# InkTime-Schematic.net
KiCad netlist of a schematic drawn in EAGLE
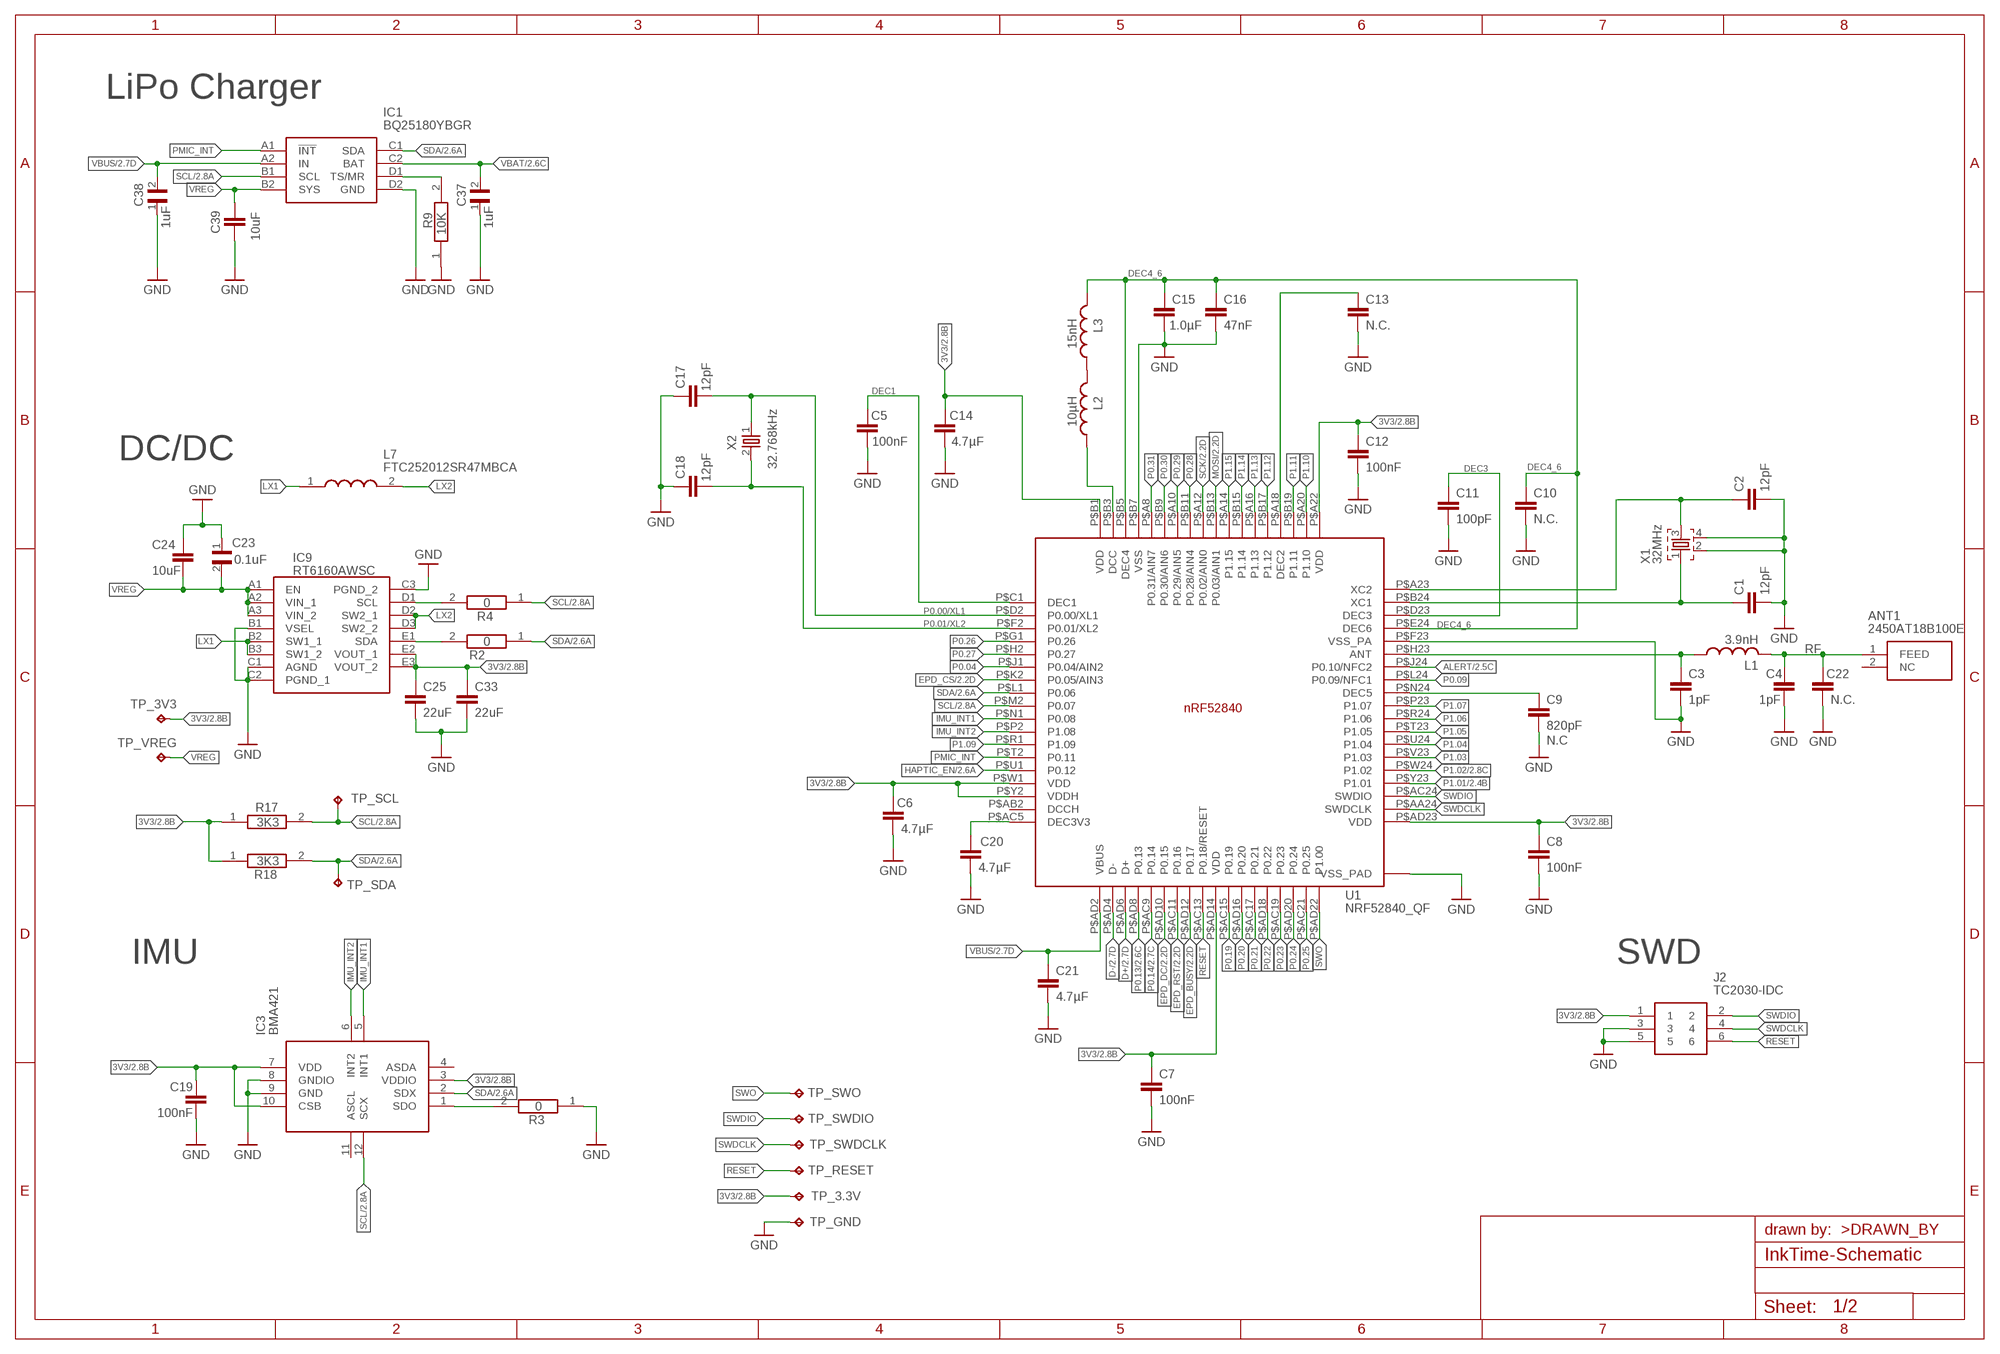
[diagram p0: schematic, sheet 1]
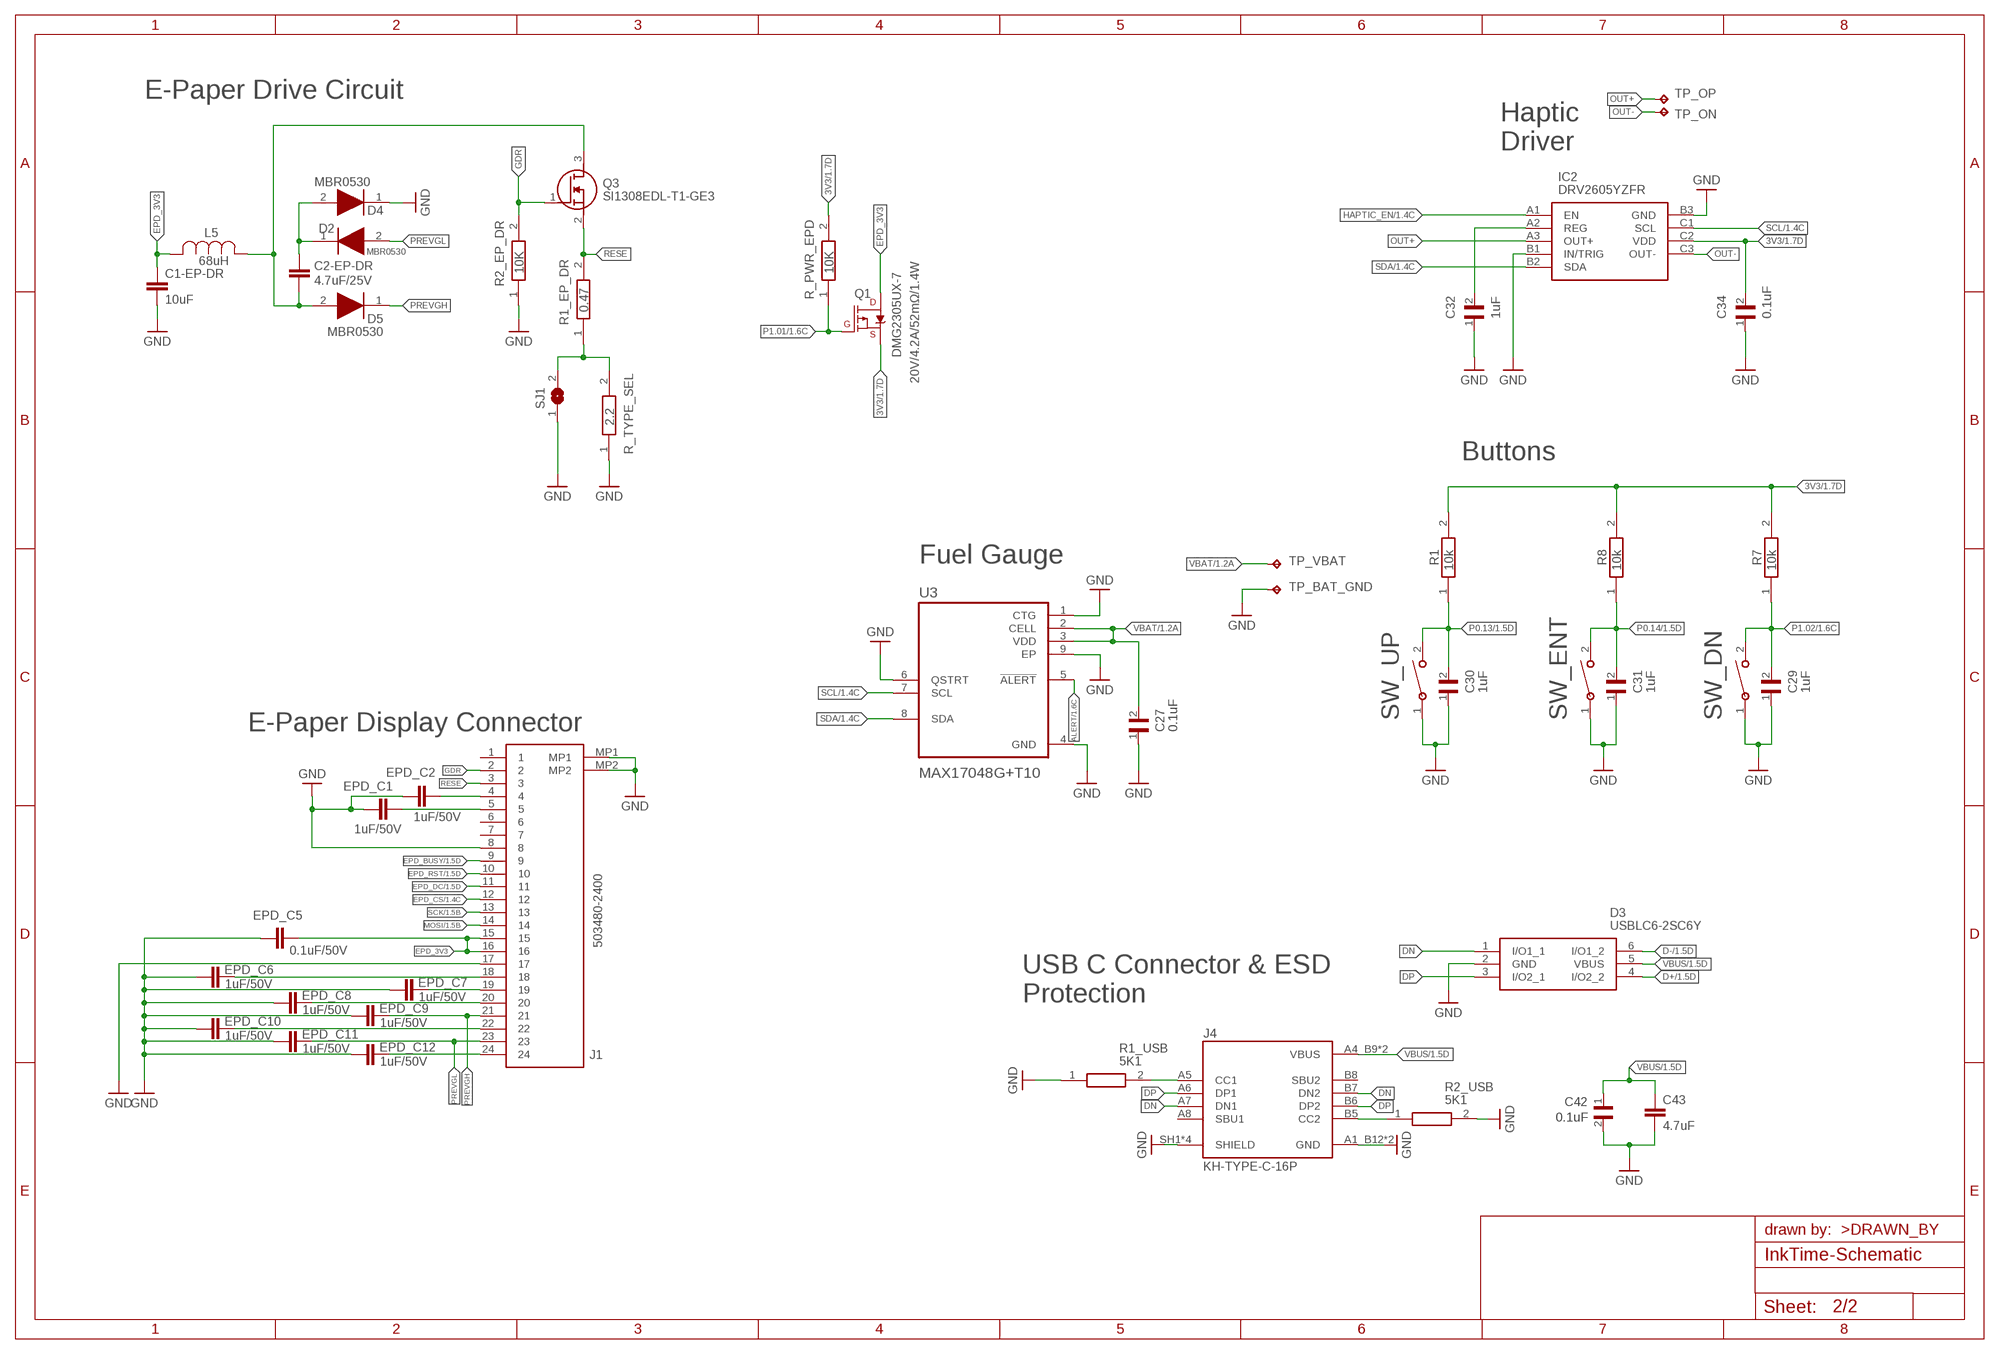
[diagram p1: schematic, sheet 2]

(export (version "E")
  (design (tool "Eeschema 10.0.6"))
  (components
    (comp (ref "ANT1")
      (value "2450AT18B100E")
      (footprint "eagle-import:2450AT18B100E_ANTC3216X140N")
      (fields (field (name "MOUSER_PART_NUMBER") "609-2450AT18B100E"))
      (libsource (lib "eagle-import") (part "2450AT18B100E_2450AT18B100E"))
    )
    (comp (ref "C1")
      (value "12pF")
      (footprint "eagle-import:NORDIC_NRF_3_RESC0201_L")
      (libsource (lib "eagle-import") (part "NORDIC_NRF_3_CAPACITOR_0201_L"))
    )
    (comp (ref "C2")
      (value "12pF")
      (footprint "eagle-import:NORDIC_NRF_3_RESC0201_L")
      (libsource (lib "eagle-import") (part "NORDIC_NRF_3_CAPACITOR_0201_L"))
    )
    (comp (ref "C3")
      (value "1pF")
      (footprint "eagle-import:NORDIC_NRF_3_RESC0201_L")
      (libsource (lib "eagle-import") (part "NORDIC_NRF_3_CAPACITOR_0201_L"))
    )
    (comp (ref "C4")
      (value "1pF")
      (footprint "eagle-import:NORDIC_NRF_3_RESC0201_L")
      (libsource (lib "eagle-import") (part "NORDIC_NRF_3_CAPACITOR_0201_L"))
    )
    (comp (ref "C5")
      (value "100nF")
      (footprint "eagle-import:NORDIC_NRF_3_RESC0201_L")
      (libsource (lib "eagle-import") (part "NORDIC_NRF_3_CAPACITOR_0201_L"))
    )
    (comp (ref "C6")
      (value "4.7µF")
      (footprint "eagle-import:NORDIC_NRF_3_RESC0402_L")
      (libsource (lib "eagle-import") (part "NORDIC_NRF_3_CAPACITOR_0402_L"))
    )
    (comp (ref "C7")
      (value "100nF")
      (footprint "eagle-import:NORDIC_NRF_3_RESC0201_L")
      (libsource (lib "eagle-import") (part "NORDIC_NRF_3_CAPACITOR_0201_L"))
    )
    (comp (ref "C8")
      (value "100nF")
      (footprint "eagle-import:NORDIC_NRF_3_RESC0201_L")
      (libsource (lib "eagle-import") (part "NORDIC_NRF_3_CAPACITOR_0201_L"))
    )
    (comp (ref "C9")
      (value "820pF")
      (footprint "eagle-import:NORDIC_NRF_3_RESC0201_L")
      (libsource (lib "eagle-import") (part "NORDIC_NRF_3_CAPACITOR_0201_L"))
    )
    (comp (ref "C10")
      (value "N.C.")
      (footprint "eagle-import:NORDIC_NRF_3_RESC0201_L")
      (libsource (lib "eagle-import") (part "NORDIC_NRF_3_CAPACITOR_0201_L"))
    )
    (comp (ref "C11")
      (value "100pF")
      (footprint "eagle-import:NORDIC_NRF_3_RESC0201_L")
      (libsource (lib "eagle-import") (part "NORDIC_NRF_3_CAPACITOR_0201_L"))
    )
    (comp (ref "C12")
      (value "100nF")
      (footprint "eagle-import:NORDIC_NRF_3_RESC0201_L")
      (libsource (lib "eagle-import") (part "NORDIC_NRF_3_CAPACITOR_0201_L"))
    )
    (comp (ref "C13")
      (value "N.C.")
      (footprint "eagle-import:NORDIC_NRF_3_RESC0201_L")
      (libsource (lib "eagle-import") (part "NORDIC_NRF_3_CAPACITOR_0201_L"))
    )
    (comp (ref "C14")
      (value "4.7µF")
      (footprint "eagle-import:NORDIC_NRF_3_RESC0402_L")
      (libsource (lib "eagle-import") (part "NORDIC_NRF_3_CAPACITOR_0402_L"))
    )
    (comp (ref "C15")
      (value "1.0µF")
      (footprint "eagle-import:NORDIC_NRF_3_RESC0402_L")
      (libsource (lib "eagle-import") (part "NORDIC_NRF_3_CAPACITOR_0402_L"))
    )
    (comp (ref "C16")
      (value "47nF")
      (footprint "eagle-import:NORDIC_NRF_3_RESC0201_L")
      (libsource (lib "eagle-import") (part "NORDIC_NRF_3_CAPACITOR_0201_L"))
    )
    (comp (ref "C17")
      (value "12pF")
      (footprint "eagle-import:NORDIC_NRF_3_RESC0201_L")
      (libsource (lib "eagle-import") (part "NORDIC_NRF_3_CAPACITOR_0201_L"))
    )
    (comp (ref "C18")
      (value "12pF")
      (footprint "eagle-import:NORDIC_NRF_3_RESC0201_L")
      (libsource (lib "eagle-import") (part "NORDIC_NRF_3_CAPACITOR_0201_L"))
    )
    (comp (ref "C19")
      (value "100nF")
      (footprint "eagle-import:NORDIC_NRF_3_RESC0201_L")
      (libsource (lib "eagle-import") (part "NORDIC_NRF_3_CAPACITOR_0201_L"))
    )
    (comp (ref "C20")
      (value "4.7µF")
      (footprint "eagle-import:NORDIC_NRF_3_RESC0402_L")
      (libsource (lib "eagle-import") (part "NORDIC_NRF_3_CAPACITOR_0402_L"))
    )
    (comp (ref "C21")
      (value "4.7µF")
      (footprint "eagle-import:NORDIC_NRF_3_RESC0402_L")
      (libsource (lib "eagle-import") (part "NORDIC_NRF_3_CAPACITOR_0402_L"))
    )
    (comp (ref "C22")
      (value "N.C.")
      (footprint "eagle-import:NORDIC_NRF_3_RESC0201_L")
      (libsource (lib "eagle-import") (part "NORDIC_NRF_3_CAPACITOR_0201_L"))
    )
    (comp (ref "C23")
      (value "0.1uF")
      (footprint "eagle-import:GRM011R60J152KE01L_1_0201")
      (libsource (lib "eagle-import") (part "GRM011R60J152KE01L_1_GRM011R60J152KE01L"))
    )
    (comp (ref "C24")
      (value "10uF")
      (footprint "eagle-import:NORDIC_NRF_3_RESC0402_L")
      (libsource (lib "eagle-import") (part "NORDIC_NRF_3_CAPACITOR_0402_L"))
    )
    (comp (ref "C25")
      (value "22uF")
      (footprint "eagle-import:NORDIC_NRF_3_RESC0402_L")
      (libsource (lib "eagle-import") (part "NORDIC_NRF_3_CAPACITOR_0402_L"))
    )
    (comp (ref "C33")
      (value "22uF")
      (footprint "eagle-import:NORDIC_NRF_3_RESC0402_L")
      (libsource (lib "eagle-import") (part "NORDIC_NRF_3_CAPACITOR_0402_L"))
    )
    (comp (ref "C37")
      (value "1uF")
      (footprint "eagle-import:GRM011R60J152KE01L_1_0201")
      (libsource (lib "eagle-import") (part "GRM011R60J152KE01L_1_GRM011R60J152KE01L"))
    )
    (comp (ref "C38")
      (value "1uF")
      (footprint "eagle-import:GRM011R60J152KE01L_1_0201")
      (libsource (lib "eagle-import") (part "GRM011R60J152KE01L_1_GRM011R60J152KE01L"))
    )
    (comp (ref "C39")
      (value "10uF")
      (footprint "eagle-import:NORDIC_NRF_3_RESC0402_L")
      (libsource (lib "eagle-import") (part "NORDIC_NRF_3_CAPACITOR_0402_L"))
    )
    (comp (ref "IC1")
      (value "BQ25180YBGR")
      (footprint "eagle-import:BQ25180YBGR_BGA8C40P2X4_100X155X50")
      (fields (field (name "MOUSER_PART_NUMBER") "595-BQ25180YBGR"))
      (libsource (lib "eagle-import") (part "BQ25180YBGR_BQ25180YBGR"))
    )
    (comp (ref "IC3")
      (value "BMA421")
      (footprint "eagle-import:BMA423_BMA423")
      (fields (field (name "ARROW_PART_NUMBER") "BMA423") (field (name "MOUSER_PART_NUMBER") "262-BMA423"))
      (libsource (lib "eagle-import") (part "BMA423_BMA423"))
    )
    (comp (ref "IC9")
      (value "RT6160AWSC")
      (footprint "eagle-import:RT6160AWSC_BGA15C40P3X5_140X230X60")
      (fields (field (name "MOUSER_PART_NUMBER") "835-RT6160AWSC"))
      (libsource (lib "eagle-import") (part "RT6160AWSC_RT6160AWSC"))
    )
    (comp (ref "J2")
      (value "TC2030-IDC")
      (footprint "eagle-import:TC2030-IDC_TC2030IDC")
      (libsource (lib "eagle-import") (part "TC2030-IDC_TC2030-IDC"))
    )
    (comp (ref "L1")
      (value "3.9nH")
      (footprint "eagle-import:NORDIC_NRF_2_RESC0402_L")
      (libsource (lib "eagle-import") (part "NORDIC_NRF_2_INDUCTOR_0402_L"))
    )
    (comp (ref "L2")
      (value "10µH")
      (footprint "eagle-import:NORDIC_NRF_2_RESC0402_L")
      (libsource (lib "eagle-import") (part "NORDIC_NRF_2_INDUCTOR_0402_L"))
    )
    (comp (ref "L3")
      (value "15nH")
      (footprint "eagle-import:NORDIC_NRF_2_RESC0402_L")
      (libsource (lib "eagle-import") (part "NORDIC_NRF_2_INDUCTOR_0402_L"))
    )
    (comp (ref "L7")
      (value "FTC252012SR47MBCA")
      (footprint "eagle-import:MLP2016SR47MT0S1_INDC2016X100N")
      (libsource (lib "eagle-import") (part "MLP2016SR47MT0S1_FTC252012SR47MBCA"))
    )
    (comp (ref "R2")
      (value "0")
      (footprint "eagle-import:CPF0201D7K68C1_0201")
      (libsource (lib "eagle-import") (part "CPF0201D7K68C1_CPF0201D7K68C1"))
    )
    (comp (ref "R3")
      (value "0")
      (footprint "eagle-import:CPF0201D7K68C1_0201")
      (libsource (lib "eagle-import") (part "CPF0201D7K68C1_CPF0201D7K68C1"))
    )
    (comp (ref "R4")
      (value "0")
      (footprint "eagle-import:CPF0201D7K68C1_0201")
      (libsource (lib "eagle-import") (part "CPF0201D7K68C1_CPF0201D7K68C1"))
    )
    (comp (ref "R9")
      (value "10K")
      (footprint "eagle-import:CPF0201D7K68C1_0201")
      (libsource (lib "eagle-import") (part "CPF0201D7K68C1_CPF0201D7K68C1"))
    )
    (comp (ref "R17")
      (value "3K3")
      (footprint "eagle-import:CPF0201D7K68C1_0201")
      (libsource (lib "eagle-import") (part "CPF0201D7K68C1_CPF0201D7K68C1"))
    )
    (comp (ref "R18")
      (value "3K3")
      (footprint "eagle-import:CPF0201D7K68C1_0201")
      (libsource (lib "eagle-import") (part "CPF0201D7K68C1_CPF0201D7K68C1"))
    )
    (comp (ref "TP_3.3V")
      (value "HECTOR_WATCH_1_TPTP20R")
      (footprint "eagle-import:HECTOR_WATCH_1_TP20R")
      (libsource (lib "eagle-import") (part "HECTOR_WATCH_1_TPTP20R"))
    )
    (comp (ref "TP_3V3")
      (value "HECTOR_WATCH_1_TPTP20R")
      (footprint "eagle-import:HECTOR_WATCH_1_TP20R")
      (libsource (lib "eagle-import") (part "HECTOR_WATCH_1_TPTP20R"))
    )
    (comp (ref "TP_GND")
      (value "HECTOR_WATCH_1_TPTP20R")
      (footprint "eagle-import:HECTOR_WATCH_1_TP20R")
      (libsource (lib "eagle-import") (part "HECTOR_WATCH_1_TPTP20R"))
    )
    (comp (ref "TP_RESET")
      (value "HECTOR_WATCH_1_TPTP20R")
      (footprint "eagle-import:HECTOR_WATCH_1_TP20R")
      (libsource (lib "eagle-import") (part "HECTOR_WATCH_1_TPTP20R"))
    )
    (comp (ref "TP_SCL")
      (value "HECTOR_WATCH_1_TPTP20R")
      (footprint "eagle-import:HECTOR_WATCH_1_TP20R")
      (libsource (lib "eagle-import") (part "HECTOR_WATCH_1_TPTP20R"))
    )
    (comp (ref "TP_SDA")
      (value "HECTOR_WATCH_1_TPTP20R")
      (footprint "eagle-import:HECTOR_WATCH_1_TP20R")
      (libsource (lib "eagle-import") (part "HECTOR_WATCH_1_TPTP20R"))
    )
    (comp (ref "TP_SWDCLK")
      (value "HECTOR_WATCH_1_TPTP20R")
      (footprint "eagle-import:HECTOR_WATCH_1_TP20R")
      (libsource (lib "eagle-import") (part "HECTOR_WATCH_1_TPTP20R"))
    )
    (comp (ref "TP_SWDIO")
      (value "HECTOR_WATCH_1_TPTP20R")
      (footprint "eagle-import:HECTOR_WATCH_1_TP20R")
      (libsource (lib "eagle-import") (part "HECTOR_WATCH_1_TPTP20R"))
    )
    (comp (ref "TP_SWO")
      (value "HECTOR_WATCH_1_TPTP20R")
      (footprint "eagle-import:HECTOR_WATCH_1_TP20R")
      (libsource (lib "eagle-import") (part "HECTOR_WATCH_1_TPTP20R"))
    )
    (comp (ref "TP_VREG")
      (value "HECTOR_WATCH_1_TPTP20R")
      (footprint "eagle-import:HECTOR_WATCH_1_TP20R")
      (libsource (lib "eagle-import") (part "HECTOR_WATCH_1_TPTP20R"))
    )
    (comp (ref "U1")
      (value "NRF52840_QF")
      (footprint "eagle-import:NORDIC_NRF_4_AQFN50P700X700X85_HS-74N")
      (libsource (lib "eagle-import") (part "NORDIC_NRF_4_NRF52840_QF"))
    )
    (comp (ref "X1")
      (value "32MHz")
      (footprint "eagle-import:NORDIC_NRF_BT-XTAL_2016_N")
      (libsource (lib "eagle-import") (part "NORDIC_NRF_XTAL_32MHZ"))
    )
    (comp (ref "X2")
      (value "32.768kHz")
      (footprint "eagle-import:NORDIC_NRF_1_XTAL_3215_N")
      (libsource (lib "eagle-import") (part "NORDIC_NRF_1_XTAL_32KHZ"))
    )
    (comp (ref "C1-EP-DR")
      (value "10uF")
      (footprint "eagle-import:NORDIC_NRF_3_RESC0402_L")
      (libsource (lib "eagle-import") (part "NORDIC_NRF_3_CAPACITOR_0402_L"))
    )
    (comp (ref "C2-EP-DR")
      (value "4.7uF/25V")
      (footprint "eagle-import:NORDIC_NRF_3_RESC0402_L")
      (libsource (lib "eagle-import") (part "NORDIC_NRF_3_CAPACITOR_0402_L"))
    )
    (comp (ref "C27")
      (value "0.1uF")
      (footprint "eagle-import:GRM011R60J152KE01L_1_0201")
      (libsource (lib "eagle-import") (part "GRM011R60J152KE01L_1_GRM011R60J152KE01L"))
    )
    (comp (ref "C29")
      (value "1uF")
      (footprint "eagle-import:GRM011R60J152KE01L_1_0201")
      (libsource (lib "eagle-import") (part "GRM011R60J152KE01L_1_GRM011R60J152KE01L"))
    )
    (comp (ref "C30")
      (value "1uF")
      (footprint "eagle-import:GRM011R60J152KE01L_1_0201")
      (libsource (lib "eagle-import") (part "GRM011R60J152KE01L_1_GRM011R60J152KE01L"))
    )
    (comp (ref "C31")
      (value "1uF")
      (footprint "eagle-import:GRM011R60J152KE01L_1_0201")
      (libsource (lib "eagle-import") (part "GRM011R60J152KE01L_1_GRM011R60J152KE01L"))
    )
    (comp (ref "C32")
      (value "1uF")
      (footprint "eagle-import:GRM011R60J152KE01L_1_0201")
      (libsource (lib "eagle-import") (part "GRM011R60J152KE01L_1_GRM011R60J152KE01L"))
    )
    (comp (ref "C34")
      (value "0.1uF")
      (footprint "eagle-import:GRM011R60J152KE01L_1_0201")
      (libsource (lib "eagle-import") (part "GRM011R60J152KE01L_1_GRM011R60J152KE01L"))
    )
    (comp (ref "C42")
      (value "0.1uF")
      (footprint "eagle-import:GRM011R60J152KE01L_1_0201")
      (libsource (lib "eagle-import") (part "GRM011R60J152KE01L_1_GRM011R60J152KE01L"))
    )
    (comp (ref "C43")
      (value "4.7uF")
      (footprint "eagle-import:NORDIC_NRF_3_RESC0402_L")
      (libsource (lib "eagle-import") (part "NORDIC_NRF_3_CAPACITOR_0402_L"))
    )
    (comp (ref "D2")
      (value "MBR0530")
      (footprint "eagle-import:ESP32_C6_LIBRARY_5_SOD3716X135N")
      (fields (field (name "MF") "ON Semiconductor"))
      (libsource (lib "eagle-import") (part "ESP32_C6_LIBRARY_5_MBR0530"))
    )
    (comp (ref "D3")
      (value "USBLC6-2SC6Y")
      (footprint "eagle-import:ESP32_C6_LIBRARY_3_SOT95P280X145-6N")
      (fields (field (name "MF") "STMicroelectronics"))
      (libsource (lib "eagle-import") (part "ESP32_C6_LIBRARY_3_USBLC6-2SC6Y"))
    )
    (comp (ref "D4")
      (value "MBR0530")
      (footprint "eagle-import:ESP32_C6_LIBRARY_5_SOD3716X135N")
      (fields (field (name "MF") "ON Semiconductor"))
      (libsource (lib "eagle-import") (part "ESP32_C6_LIBRARY_5_MBR0530"))
    )
    (comp (ref "D5")
      (value "MBR0530")
      (footprint "eagle-import:ESP32_C6_LIBRARY_5_SOD3716X135N")
      (fields (field (name "MF") "ON Semiconductor"))
      (libsource (lib "eagle-import") (part "ESP32_C6_LIBRARY_5_MBR0530"))
    )
    (comp (ref "EPD_C1")
      (value "1uF/50V")
      (footprint "eagle-import:NORDIC_NRF_3_RESC0402_L")
      (libsource (lib "eagle-import") (part "NORDIC_NRF_3_CAPACITOR_0402_L"))
    )
    (comp (ref "EPD_C2")
      (value "1uF/50V")
      (footprint "eagle-import:NORDIC_NRF_3_RESC0402_L")
      (libsource (lib "eagle-import") (part "NORDIC_NRF_3_CAPACITOR_0402_L"))
    )
    (comp (ref "EPD_C5")
      (value "0.1uF/50V")
      (footprint "eagle-import:NORDIC_NRF_3_RESC0201_L")
      (libsource (lib "eagle-import") (part "NORDIC_NRF_3_CAPACITOR_0201_L"))
    )
    (comp (ref "EPD_C6")
      (value "1uF/50V")
      (footprint "eagle-import:NORDIC_NRF_3_RESC0402_L")
      (libsource (lib "eagle-import") (part "NORDIC_NRF_3_CAPACITOR_0402_L"))
    )
    (comp (ref "EPD_C7")
      (value "1uF/50V")
      (footprint "eagle-import:NORDIC_NRF_3_RESC0402_L")
      (libsource (lib "eagle-import") (part "NORDIC_NRF_3_CAPACITOR_0402_L"))
    )
    (comp (ref "EPD_C8")
      (value "1uF/50V")
      (footprint "eagle-import:NORDIC_NRF_3_RESC0402_L")
      (libsource (lib "eagle-import") (part "NORDIC_NRF_3_CAPACITOR_0402_L"))
    )
    (comp (ref "EPD_C9")
      (value "1uF/50V")
      (footprint "eagle-import:NORDIC_NRF_3_RESC0402_L")
      (libsource (lib "eagle-import") (part "NORDIC_NRF_3_CAPACITOR_0402_L"))
    )
    (comp (ref "EPD_C10")
      (value "1uF/50V")
      (footprint "eagle-import:NORDIC_NRF_3_RESC0402_L")
      (libsource (lib "eagle-import") (part "NORDIC_NRF_3_CAPACITOR_0402_L"))
    )
    (comp (ref "EPD_C11")
      (value "1uF/50V")
      (footprint "eagle-import:NORDIC_NRF_3_RESC0402_L")
      (libsource (lib "eagle-import") (part "NORDIC_NRF_3_CAPACITOR_0402_L"))
    )
    (comp (ref "EPD_C12")
      (value "1uF/50V")
      (footprint "eagle-import:NORDIC_NRF_3_RESC0402_L")
      (libsource (lib "eagle-import") (part "NORDIC_NRF_3_CAPACITOR_0402_L"))
    )
    (comp (ref "IC2")
      (value "DRV2605YZFR")
      (footprint "eagle-import:DRV2605YZFR_BGA9C50P3X3_144X144X62")
      (libsource (lib "eagle-import") (part "DRV2605YZFR_DRV2605YZFR"))
    )
    (comp (ref "J1")
      (value "503480-2400")
      (footprint "eagle-import:503480-2400_5034802400")
      (fields (field (name "MOUSER_PART_NUMBER") "538-503480-2400"))
      (libsource (lib "eagle-import") (part "503480-2400_503480-2400"))
    )
    (comp (ref "J4")
      (value "KH-TYPE-C-16P")
      (footprint "eagle-import:KH-TYPE-C-16P_KINGHELM_KH-TYPE-C-16P")
      (fields (field (name "MF") "kinghelm"))
      (libsource (lib "eagle-import") (part "KH-TYPE-C-16P_KH-TYPE-C-16P"))
    )
    (comp (ref "L5")
      (value "68uH")
      (footprint "eagle-import:ESP32_C6_LIBRARY_2_IND_4828-WE-TPC_WRE")
      (fields
        (field (name "MANUFACTURER_PART_NUMBER") "744043680")
        (field (name "COPYRIGHT") "Copyright (C) 2024 Ultra Librarian. All rights reserved.")
      )
      (libsource (lib "eagle-import") (part "ESP32_C6_LIBRARY_2_744043680IND_4828-WE-TPC_WRE"))
    )
    (comp (ref "Q1")
      (value "20V/4.2A/52mΩ/1.4W")
      (footprint "eagle-import:ESP32_C6_LIBRARY_4_ESP32_C6_LIBRARY_4_ESP32_C6_LIBRARY_4_ESP32_C6_LIBRARY_4_ESP32_WROVER_SPARKFUN-DISCRETESEMI_SOT23-3")
      (libsource (lib "eagle-import") (part "ESP32_C6_LIBRARY_4_ESP32_WROVER_SPARKFUN-DISCRETESEMI_MOSFET_PCH-DMG2305UX-7"))
    )
    (comp (ref "Q3")
      (value "SI1308EDL-T1-GE3")
      (footprint "eagle-import:ESP32_C6_LIBRARY_6_SOT65P210X110-3N")
      (fields (field (name "MF") "Vishay Siliconix"))
      (libsource (lib "eagle-import") (part "ESP32_C6_LIBRARY_6_SI1308EDL-T1-GE3"))
    )
    (comp (ref "R1")
      (value "10k")
      (footprint "eagle-import:CPF0201D7K68C1_0201")
      (libsource (lib "eagle-import") (part "CPF0201D7K68C1_CPF0201D7K68C1"))
    )
    (comp (ref "R1_EP_DR")
      (value "0.47")
      (footprint "eagle-import:CPF0201D7K68C1_0201")
      (libsource (lib "eagle-import") (part "CPF0201D7K68C1_CPF0201D7K68C1"))
    )
    (comp (ref "R1_USB")
      (value "5K1")
      (footprint "eagle-import:CPF0201D7K68C1_0201")
      (libsource (lib "eagle-import") (part "CPF0201D7K68C1_CPF0201D7K68C1"))
    )
    (comp (ref "R2_EP_DR")
      (value "10K")
      (footprint "eagle-import:CPF0201D7K68C1_0201")
      (libsource (lib "eagle-import") (part "CPF0201D7K68C1_CPF0201D7K68C1"))
    )
    (comp (ref "R2_USB")
      (value "5K1")
      (footprint "eagle-import:CPF0201D7K68C1_0201")
      (libsource (lib "eagle-import") (part "CPF0201D7K68C1_CPF0201D7K68C1"))
    )
    (comp (ref "R7")
      (value "10k")
      (footprint "eagle-import:CPF0201D7K68C1_0201")
      (libsource (lib "eagle-import") (part "CPF0201D7K68C1_CPF0201D7K68C1"))
    )
    (comp (ref "R8")
      (value "10k")
      (footprint "eagle-import:CPF0201D7K68C1_0201")
      (libsource (lib "eagle-import") (part "CPF0201D7K68C1_CPF0201D7K68C1"))
    )
    (comp (ref "R_PWR_EPD")
      (value "10K")
      (footprint "eagle-import:CPF0201D7K68C1_0201")
      (libsource (lib "eagle-import") (part "CPF0201D7K68C1_CPF0201D7K68C1"))
    )
    (comp (ref "R_TYPE_SEL")
      (value "2.2")
      (footprint "eagle-import:CPF0201D7K68C1_0201")
      (libsource (lib "eagle-import") (part "CPF0201D7K68C1_CPF0201D7K68C1"))
    )
    (comp (ref "SJ1")
      (value "ESP32_C6_LIBRARY_7_JUMPER_SJ")
      (footprint "eagle-import:ESP32_C6_LIBRARY_7_JUMPER_SJ")
      (libsource (lib "eagle-import") (part "ESP32_C6_LIBRARY_7_JUMPER_SJ"))
    )
    (comp (ref "SW_DN")
      (value "2025-10-22_07-23-44_LIBRARY_EVP-AKE31ASW_EVP-AKE31A_PAN")
      (footprint "eagle-import:2025-10-22_07-23-44_LIBRARY_SW_EVP-AKE31A_PAN")
      (fields
        (field (name "MANUFACTURER_PART_NUMBER") "EVP-AKE31A")
        (field (name "COPYRIGHT") "Copyright (C) 2025 Ultra Librarian. All rights reserved.")
      )
      (libsource (lib "eagle-import") (part "2025-10-22_07-23-44_LIBRARY_EVP-AKE31ASW_EVP-AKE31A_PAN"))
    )
    (comp (ref "SW_ENT")
      (value "2025-10-22_07-23-44_LIBRARY_EVP-AKE31ASW_EVP-AKE31A_PAN")
      (footprint "eagle-import:2025-10-22_07-23-44_LIBRARY_SW_EVP-AKE31A_PAN")
      (fields
        (field (name "MANUFACTURER_PART_NUMBER") "EVP-AKE31A")
        (field (name "COPYRIGHT") "Copyright (C) 2025 Ultra Librarian. All rights reserved.")
      )
      (libsource (lib "eagle-import") (part "2025-10-22_07-23-44_LIBRARY_EVP-AKE31ASW_EVP-AKE31A_PAN"))
    )
    (comp (ref "SW_UP")
      (value "2025-10-22_07-23-44_LIBRARY_EVP-AKE31ASW_EVP-AKE31A_PAN")
      (footprint "eagle-import:2025-10-22_07-23-44_LIBRARY_SW_EVP-AKE31A_PAN")
      (fields
        (field (name "MANUFACTURER_PART_NUMBER") "EVP-AKE31A")
        (field (name "COPYRIGHT") "Copyright (C) 2025 Ultra Librarian. All rights reserved.")
      )
      (libsource (lib "eagle-import") (part "2025-10-22_07-23-44_LIBRARY_EVP-AKE31ASW_EVP-AKE31A_PAN"))
    )
    (comp (ref "TP_BAT_GND")
      (value "HECTOR_WATCH_1_TPTP20R")
      (footprint "eagle-import:HECTOR_WATCH_1_TP20R")
      (libsource (lib "eagle-import") (part "HECTOR_WATCH_1_TPTP20R"))
    )
    (comp (ref "TP_ON")
      (value "HECTOR_WATCH_1_TPTP20R")
      (footprint "eagle-import:HECTOR_WATCH_1_TP20R")
      (libsource (lib "eagle-import") (part "HECTOR_WATCH_1_TPTP20R"))
    )
    (comp (ref "TP_OP")
      (value "HECTOR_WATCH_1_TPTP20R")
      (footprint "eagle-import:HECTOR_WATCH_1_TP20R")
      (libsource (lib "eagle-import") (part "HECTOR_WATCH_1_TPTP20R"))
    )
    (comp (ref "TP_VBAT")
      (value "HECTOR_WATCH_1_TPTP20R")
      (footprint "eagle-import:HECTOR_WATCH_1_TP20R")
      (libsource (lib "eagle-import") (part "HECTOR_WATCH_1_TPTP20R"))
    )
    (comp (ref "U3")
      (value "MAX17048G+T10")
      (footprint "eagle-import:ESP32_C6_LIBRARY_SON50P200X200X80-9N")
      (fields (field (name "MF") "Analog Devices"))
      (libsource (lib "eagle-import") (part "ESP32_C6_LIBRARY_MAX17048G+T10"))
    )
  )
  (nets
    (net (code "1") (name "3V3") (class "Default")
      (node (ref "C12") (pin "1") (pinfunction "1_1") (pintype "passive"))
      (node (ref "C14") (pin "2") (pinfunction "2_2") (pintype "passive"))
      (node (ref "C19") (pin "1") (pinfunction "1_1") (pintype "passive"))
      (node (ref "C25") (pin "1") (pinfunction "1_1") (pintype "passive"))
      (node (ref "C33") (pin "1") (pinfunction "1_1") (pintype "passive"))
      (node (ref "C34") (pin "2") (pinfunction "2_2") (pintype "passive"))
      (node (ref "C6") (pin "2") (pinfunction "2_2") (pintype "passive"))
      (node (ref "C7") (pin "1") (pinfunction "1_1") (pintype "passive"))
      (node (ref "C8") (pin "1") (pinfunction "1_1") (pintype "passive"))
      (node (ref "IC2") (pin "C2") (pinfunction "VDD_C2") (pintype "bidirectional"))
      (node (ref "IC3") (pin "10") (pinfunction "CSB_10") (pintype "bidirectional"))
      (node (ref "IC3") (pin "3") (pinfunction "VDDIO_3") (pintype "bidirectional"))
      (node (ref "IC3") (pin "7") (pinfunction "VDD_7") (pintype "bidirectional"))
      (node (ref "IC9") (pin "E2") (pinfunction "VOUT_1_E2") (pintype "bidirectional"))
      (node (ref "IC9") (pin "E3") (pinfunction "VOUT_2_E3") (pintype "bidirectional"))
      (node (ref "J2") (pin "1") (pinfunction "1_1") (pintype "bidirectional"))
      (node (ref "Q1") (pin "2") (pinfunction "S_2") (pintype "bidirectional"))
      (node (ref "R1") (pin "2") (pinfunction "2_2") (pintype "bidirectional"))
      (node (ref "R17") (pin "1") (pinfunction "1_1") (pintype "bidirectional"))
      (node (ref "R18") (pin "1") (pinfunction "1_1") (pintype "bidirectional"))
      (node (ref "R7") (pin "2") (pinfunction "2_2") (pintype "bidirectional"))
      (node (ref "R8") (pin "2") (pinfunction "2_2") (pintype "bidirectional"))
      (node (ref "R_PWR_EPD") (pin "2") (pinfunction "2_2") (pintype "bidirectional"))
      (node (ref "TP_3.3V") (pin "TP") (pinfunction "TP_TP") (pintype "input"))
      (node (ref "TP_3V3") (pin "TP") (pinfunction "TP_TP") (pintype "input"))
      (node (ref "U1") (pin "P$A22") (pinfunction "VDD_P$A22") (pintype "power_in"))
      (node (ref "U1") (pin "P$AD14") (pinfunction "VDD_P$AD14") (pintype "power_in"))
      (node (ref "U1") (pin "P$AD23") (pinfunction "VDD_P$AD23") (pintype "power_in"))
      (node (ref "U1") (pin "P$B1") (pinfunction "VDD_P$B1") (pintype "power_in"))
      (node (ref "U1") (pin "P$W1") (pinfunction "VDD_P$W1") (pintype "power_in"))
      (node (ref "U1") (pin "P$Y2") (pinfunction "VDDH_P$Y2") (pintype "power_in"))
    )
    (net (code "2") (name "ALERT") (class "Default")
      (node (ref "U1") (pin "P$J24") (pinfunction "P0.10/NFC2_P$J24") (pintype "bidirectional"))
      (node (ref "U3") (pin "5") (pinfunction "~{ALERT}_5") (pintype "output"))
    )
    (net (code "3") (name "D+") (class "Default")
      (node (ref "D3") (pin "4") (pinfunction "I/O2_2_4") (pintype "bidirectional"))
      (node (ref "U1") (pin "P$AD6") (pinfunction "D+_P$AD6") (pintype "bidirectional"))
    )
    (net (code "4") (name "D-") (class "Default")
      (node (ref "D3") (pin "6") (pinfunction "I/O1_2_6") (pintype "bidirectional"))
      (node (ref "U1") (pin "P$AD4") (pinfunction "D-_P$AD4") (pintype "bidirectional"))
    )
    (net (code "5") (name "DN") (class "Default")
      (node (ref "D3") (pin "1") (pinfunction "I/O1_1_1") (pintype "bidirectional"))
      (node (ref "J4") (pin "A7") (pinfunction "DN1_A7") (pintype "bidirectional"))
      (node (ref "J4") (pin "B7") (pinfunction "DN2_B7") (pintype "bidirectional"))
    )
    (net (code "6") (name "DP") (class "Default")
      (node (ref "D3") (pin "3") (pinfunction "I/O2_1_3") (pintype "bidirectional"))
      (node (ref "J4") (pin "A6") (pinfunction "DP1_A6") (pintype "bidirectional"))
      (node (ref "J4") (pin "B6") (pinfunction "DP2_B6") (pintype "bidirectional"))
    )
    (net (code "7") (name "EPD_3V3") (class "Default")
      (node (ref "C1-EP-DR") (pin "1") (pinfunction "1_1") (pintype "passive"))
      (node (ref "EPD_C5") (pin "2") (pinfunction "2_2") (pintype "passive"))
      (node (ref "J1") (pin "15") (pinfunction "15_15") (pintype "bidirectional"))
      (node (ref "J1") (pin "16") (pinfunction "16_16") (pintype "bidirectional"))
      (node (ref "L5") (pin "2") (pinfunction "2_2") (pintype "passive"))
      (node (ref "Q1") (pin "3") (pinfunction "D_3") (pintype "bidirectional"))
    )
    (net (code "8") (name "EPD_BUSY") (class "Default")
      (node (ref "J1") (pin "9") (pinfunction "9_9") (pintype "bidirectional"))
      (node (ref "U1") (pin "P$AD12") (pinfunction "P0.17_P$AD12") (pintype "bidirectional"))
    )
    (net (code "9") (name "EPD_CS") (class "Default")
      (node (ref "J1") (pin "12") (pinfunction "12_12") (pintype "bidirectional"))
      (node (ref "U1") (pin "P$K2") (pinfunction "P0.05/AIN3_P$K2") (pintype "bidirectional"))
    )
    (net (code "10") (name "EPD_DC") (class "Default")
      (node (ref "J1") (pin "11") (pinfunction "11_11") (pintype "bidirectional"))
      (node (ref "U1") (pin "P$AD10") (pinfunction "P0.15_P$AD10") (pintype "bidirectional"))
    )
    (net (code "11") (name "EPD_RST") (class "Default")
      (node (ref "J1") (pin "10") (pinfunction "10_10") (pintype "bidirectional"))
      (node (ref "U1") (pin "P$AC11") (pinfunction "P0.16_P$AC11") (pintype "bidirectional"))
    )
    (net (code "12") (name "GDR") (class "Default")
      (node (ref "J1") (pin "2") (pinfunction "2_2") (pintype "bidirectional"))
      (node (ref "Q3") (pin "1") (pinfunction "G_1") (pintype "bidirectional"))
      (node (ref "R2_EP_DR") (pin "2") (pinfunction "2_2") (pintype "bidirectional"))
    )
    (net (code "13") (name "GND") (class "Default")
      (node (ref "C1") (pin "2") (pinfunction "2_2") (pintype "passive"))
      (node (ref "C1-EP-DR") (pin "2") (pinfunction "2_2") (pintype "passive"))
      (node (ref "C10") (pin "2") (pinfunction "2_2") (pintype "passive"))
      (node (ref "C11") (pin "2") (pinfunction "2_2") (pintype "passive"))
      (node (ref "C12") (pin "2") (pinfunction "2_2") (pintype "passive"))
      (node (ref "C13") (pin "2") (pinfunction "2_2") (pintype "passive"))
      (node (ref "C14") (pin "1") (pinfunction "1_1") (pintype "passive"))
      (node (ref "C15") (pin "2") (pinfunction "2_2") (pintype "passive"))
      (node (ref "C16") (pin "2") (pinfunction "2_2") (pintype "passive"))
      (node (ref "C17") (pin "1") (pinfunction "1_1") (pintype "passive"))
      (node (ref "C18") (pin "1") (pinfunction "1_1") (pintype "passive"))
      (node (ref "C19") (pin "2") (pinfunction "2_2") (pintype "passive"))
      (node (ref "C2") (pin "2") (pinfunction "2_2") (pintype "passive"))
      (node (ref "C20") (pin "1") (pinfunction "1_1") (pintype "passive"))
      (node (ref "C21") (pin "2") (pinfunction "2_2") (pintype "passive"))
      (node (ref "C22") (pin "2") (pinfunction "2_2") (pintype "passive"))
      (node (ref "C23") (pin "1") (pinfunction "1_1") (pintype "passive"))
      (node (ref "C24") (pin "1") (pinfunction "1_1") (pintype "passive"))
      (node (ref "C25") (pin "2") (pinfunction "2_2") (pintype "passive"))
      (node (ref "C27") (pin "1") (pinfunction "1_1") (pintype "passive"))
      (node (ref "C29") (pin "1") (pinfunction "1_1") (pintype "passive"))
      (node (ref "C3") (pin "2") (pinfunction "2_2") (pintype "passive"))
      (node (ref "C30") (pin "1") (pinfunction "1_1") (pintype "passive"))
      (node (ref "C31") (pin "1") (pinfunction "1_1") (pintype "passive"))
      (node (ref "C32") (pin "1") (pinfunction "1_1") (pintype "passive"))
      (node (ref "C33") (pin "2") (pinfunction "2_2") (pintype "passive"))
      (node (ref "C34") (pin "1") (pinfunction "1_1") (pintype "passive"))
      (node (ref "C37") (pin "1") (pinfunction "1_1") (pintype "passive"))
      (node (ref "C38") (pin "1") (pinfunction "1_1") (pintype "passive"))
      (node (ref "C39") (pin "2") (pinfunction "2_2") (pintype "passive"))
      (node (ref "C4") (pin "2") (pinfunction "2_2") (pintype "passive"))
      (node (ref "C42") (pin "2") (pinfunction "2_2") (pintype "passive"))
      (node (ref "C43") (pin "2") (pinfunction "2_2") (pintype "passive"))
      (node (ref "C5") (pin "1") (pinfunction "1_1") (pintype "passive"))
      (node (ref "C6") (pin "1") (pinfunction "1_1") (pintype "passive"))
      (node (ref "C7") (pin "2") (pinfunction "2_2") (pintype "passive"))
      (node (ref "C8") (pin "2") (pinfunction "2_2") (pintype "passive"))
      (node (ref "C9") (pin "2") (pinfunction "2_2") (pintype "passive"))
      (node (ref "D3") (pin "2") (pinfunction "GND_2") (pintype "bidirectional"))
      (node (ref "D4") (pin "1") (pinfunction "K_1") (pintype "bidirectional"))
      (node (ref "EPD_C1") (pin "1") (pinfunction "1_1") (pintype "passive"))
      (node (ref "EPD_C10") (pin "1") (pinfunction "1_1") (pintype "passive"))
      (node (ref "EPD_C11") (pin "1") (pinfunction "1_1") (pintype "passive"))
      (node (ref "EPD_C12") (pin "1") (pinfunction "1_1") (pintype "passive"))
      (node (ref "EPD_C2") (pin "1") (pinfunction "1_1") (pintype "passive"))
      (node (ref "EPD_C5") (pin "1") (pinfunction "1_1") (pintype "passive"))
      (node (ref "EPD_C6") (pin "1") (pinfunction "1_1") (pintype "passive"))
      (node (ref "EPD_C7") (pin "1") (pinfunction "1_1") (pintype "passive"))
      (node (ref "EPD_C8") (pin "1") (pinfunction "1_1") (pintype "passive"))
      (node (ref "EPD_C9") (pin "1") (pinfunction "1_1") (pintype "passive"))
      (node (ref "IC1") (pin "D2") (pinfunction "GND_D2") (pintype "bidirectional"))
      (node (ref "IC2") (pin "B1") (pinfunction "IN/TRIG_B1") (pintype "bidirectional"))
      (node (ref "IC2") (pin "B3") (pinfunction "GND_B3") (pintype "bidirectional"))
      (node (ref "IC3") (pin "8") (pinfunction "GNDIO_8") (pintype "bidirectional"))
      (node (ref "IC3") (pin "9") (pinfunction "GND_9") (pintype "bidirectional"))
      (node (ref "IC9") (pin "B1") (pinfunction "VSEL_B1") (pintype "bidirectional"))
      (node (ref "IC9") (pin "C1") (pinfunction "AGND_C1") (pintype "bidirectional"))
      (node (ref "IC9") (pin "C2") (pinfunction "PGND_1_C2") (pintype "bidirectional"))
      (node (ref "IC9") (pin "C3") (pinfunction "PGND_2_C3") (pintype "bidirectional"))
      (node (ref "J1") (pin "17") (pinfunction "17_17") (pintype "bidirectional"))
      (node (ref "J1") (pin "8") (pinfunction "8_8") (pintype "bidirectional"))
      (node (ref "J1") (pin "MP1") (pinfunction "MP1_MP1") (pintype "bidirectional"))
      (node (ref "J1") (pin "MP2") (pinfunction "MP2_MP2") (pintype "bidirectional"))
      (node (ref "J2") (pin "3") (pinfunction "3_3") (pintype "bidirectional"))
      (node (ref "J2") (pin "5") (pinfunction "5_5") (pintype "bidirectional"))
      (node (ref "J4") (pin "A12_B1") (pinfunction "GND_A12_B1") (pintype "power_in"))
      (node (ref "J4") (pin "A1_B12") (pinfunction "GND_A1_B12") (pintype "power_in"))
      (node (ref "J4") (pin "SH1") (pinfunction "SHIELD_SH1") (pintype "passive"))
      (node (ref "J4") (pin "SH2") (pinfunction "SHIELD_SH2") (pintype "passive"))
      (node (ref "J4") (pin "SH3") (pinfunction "SHIELD_SH3") (pintype "passive"))
      (node (ref "J4") (pin "SH4") (pinfunction "SHIELD_SH4") (pintype "passive"))
      (node (ref "R1_USB") (pin "1") (pinfunction "1_1") (pintype "bidirectional"))
      (node (ref "R2_EP_DR") (pin "1") (pinfunction "1_1") (pintype "bidirectional"))
      (node (ref "R2_USB") (pin "2") (pinfunction "2_2") (pintype "bidirectional"))
      (node (ref "R3") (pin "1") (pinfunction "1_1") (pintype "bidirectional"))
      (node (ref "R9") (pin "1") (pinfunction "1_1") (pintype "bidirectional"))
      (node (ref "R_TYPE_SEL") (pin "1") (pinfunction "1_1") (pintype "bidirectional"))
      (node (ref "SJ1") (pin "1") (pinfunction "1_1") (pintype "passive"))
      (node (ref "SW_DN") (pin "1") (pinfunction "1_1") (pintype "passive"))
      (node (ref "SW_ENT") (pin "1") (pinfunction "1_1") (pintype "passive"))
      (node (ref "SW_UP") (pin "1") (pinfunction "1_1") (pintype "passive"))
      (node (ref "TP_BAT_GND") (pin "TP") (pinfunction "TP_TP") (pintype "input"))
      (node (ref "TP_GND") (pin "TP") (pinfunction "TP_TP") (pintype "input"))
      (node (ref "U1") (pin "P$74") (pinfunction "VSS_PAD_P$74") (pintype "bidirectional"))
      (node (ref "U1") (pin "P$75") (pinfunction "VSS_PAD_P$75") (pintype "bidirectional"))
      (node (ref "U1") (pin "P$76") (pinfunction "VSS_PAD_P$76") (pintype "bidirectional"))
      (node (ref "U1") (pin "P$77") (pinfunction "VSS_PAD_P$77") (pintype "bidirectional"))
      (node (ref "U1") (pin "P$78") (pinfunction "VSS_PAD_P$78") (pintype "bidirectional"))
      (node (ref "U1") (pin "P$79") (pinfunction "VSS_PAD_P$79") (pintype "bidirectional"))
      (node (ref "U1") (pin "P$80") (pinfunction "VSS_PAD_P$80") (pintype "bidirectional"))
      (node (ref "U1") (pin "P$81") (pinfunction "VSS_PAD_P$81") (pintype "bidirectional"))
      (node (ref "U1") (pin "P$82") (pinfunction "VSS_PAD_P$82") (pintype "bidirectional"))
      (node (ref "U1") (pin "P$83") (pinfunction "VSS_PAD_P$83") (pintype "bidirectional"))
      (node (ref "U1") (pin "P$84") (pinfunction "VSS_PAD_P$84") (pintype "bidirectional"))
      (node (ref "U1") (pin "P$85") (pinfunction "VSS_PAD_P$85") (pintype "bidirectional"))
      (node (ref "U1") (pin "P$86") (pinfunction "VSS_PAD_P$86") (pintype "bidirectional"))
      (node (ref "U1") (pin "P$87") (pinfunction "VSS_PAD_P$87") (pintype "bidirectional"))
      (node (ref "U1") (pin "P$88") (pinfunction "VSS_PAD_P$88") (pintype "bidirectional"))
      (node (ref "U1") (pin "P$89") (pinfunction "VSS_PAD_P$89") (pintype "bidirectional"))
      (node (ref "U1") (pin "P$90") (pinfunction "VSS_PAD_P$90") (pintype "bidirectional"))
      (node (ref "U1") (pin "P$B7") (pinfunction "VSS_P$B7") (pintype "power_in"))
      (node (ref "U1") (pin "P$F23") (pinfunction "VSS_PA_P$F23") (pintype "bidirectional"))
      (node (ref "U3") (pin "1") (pinfunction "CTG_1") (pintype "power_in"))
      (node (ref "U3") (pin "4") (pinfunction "GND_4") (pintype "power_in"))
      (node (ref "U3") (pin "6") (pinfunction "QSTRT_6") (pintype "input"))
      (node (ref "U3") (pin "9") (pinfunction "EP_9") (pintype "power_in"))
      (node (ref "X1") (pin "2") (pinfunction "2_2") (pintype "passive"))
      (node (ref "X1") (pin "4") (pinfunction "4_4") (pintype "passive"))
    )
    (net (code "14") (name "HAPTIC_EN") (class "Default")
      (node (ref "IC2") (pin "A1") (pinfunction "EN_A1") (pintype "bidirectional"))
      (node (ref "U1") (pin "P$U1") (pinfunction "P0.12_P$U1") (pintype "bidirectional"))
    )
    (net (code "15") (name "IMU_INT1") (class "Default")
      (node (ref "IC3") (pin "5") (pinfunction "INT1_5") (pintype "bidirectional"))
      (node (ref "U1") (pin "P$N1") (pinfunction "P0.08_P$N1") (pintype "bidirectional"))
    )
    (net (code "16") (name "IMU_INT2") (class "Default")
      (node (ref "IC3") (pin "6") (pinfunction "INT2_6") (pintype "bidirectional"))
      (node (ref "U1") (pin "P$P2") (pinfunction "P1.08_P$P2") (pintype "bidirectional"))
    )
    (net (code "17") (name "LX1") (class "Default")
      (node (ref "IC9") (pin "B2") (pinfunction "SW1_1_B2") (pintype "bidirectional"))
      (node (ref "IC9") (pin "B3") (pinfunction "SW1_2_B3") (pintype "bidirectional"))
      (node (ref "L7") (pin "1") (pinfunction "1_1") (pintype "bidirectional"))
    )
    (net (code "18") (name "LX2") (class "Default")
      (node (ref "IC9") (pin "D2") (pinfunction "SW2_1_D2") (pintype "bidirectional"))
      (node (ref "IC9") (pin "D3") (pinfunction "SW2_2_D3") (pintype "bidirectional"))
      (node (ref "L7") (pin "2") (pinfunction "2_2") (pintype "bidirectional"))
    )
    (net (code "19") (name "MOSI") (class "Default")
      (node (ref "J1") (pin "14") (pinfunction "14_14") (pintype "bidirectional"))
      (node (ref "U1") (pin "P$B13") (pinfunction "P0.03/AIN1_P$B13") (pintype "bidirectional"))
    )
    (net (code "20") (name "Net-(ANT1-FEED)") (class "Default")
      (node (ref "ANT1") (pin "1") (pinfunction "FEED_1") (pintype "input"))
      (node (ref "C22") (pin "1") (pinfunction "1_1") (pintype "passive"))
      (node (ref "C4") (pin "1") (pinfunction "1_1") (pintype "passive"))
      (node (ref "L1") (pin "2") (pinfunction "2_2") (pintype "passive"))
    )
    (net (code "21") (name "Net-(D2-K)") (class "Default")
      (node (ref "C2-EP-DR") (pin "1") (pinfunction "1_1") (pintype "passive"))
      (node (ref "D2") (pin "1") (pinfunction "K_1") (pintype "bidirectional"))
      (node (ref "D4") (pin "2") (pinfunction "A_2") (pintype "bidirectional"))
    )
    (net (code "22") (name "Net-(D5-A)") (class "Default")
      (node (ref "C2-EP-DR") (pin "2") (pinfunction "2_2") (pintype "passive"))
      (node (ref "D5") (pin "2") (pinfunction "A_2") (pintype "bidirectional"))
      (node (ref "L5") (pin "1") (pinfunction "1_1") (pintype "passive"))
      (node (ref "Q3") (pin "3") (pinfunction "D_3") (pintype "bidirectional"))
    )
    (net (code "23") (name "Net-(EPD_C1-Pad2)") (class "Default")
      (node (ref "EPD_C1") (pin "2") (pinfunction "2_2") (pintype "passive"))
      (node (ref "J1") (pin "5") (pinfunction "5_5") (pintype "bidirectional"))
    )
    (net (code "24") (name "Net-(EPD_C2-Pad2)") (class "Default")
      (node (ref "EPD_C2") (pin "2") (pinfunction "2_2") (pintype "passive"))
      (node (ref "J1") (pin "4") (pinfunction "4_4") (pintype "bidirectional"))
    )
    (net (code "25") (name "Net-(EPD_C6-Pad2)") (class "Default")
      (node (ref "EPD_C6") (pin "2") (pinfunction "2_2") (pintype "passive"))
      (node (ref "J1") (pin "18") (pinfunction "18_18") (pintype "bidirectional"))
    )
    (net (code "26") (name "Net-(EPD_C7-Pad2)") (class "Default")
      (node (ref "EPD_C7") (pin "2") (pinfunction "2_2") (pintype "passive"))
      (node (ref "J1") (pin "19") (pinfunction "19_19") (pintype "bidirectional"))
    )
    (net (code "27") (name "Net-(EPD_C8-Pad2)") (class "Default")
      (node (ref "EPD_C8") (pin "2") (pinfunction "2_2") (pintype "passive"))
      (node (ref "J1") (pin "20") (pinfunction "20_20") (pintype "bidirectional"))
    )
    (net (code "28") (name "Net-(EPD_C10-Pad2)") (class "Default")
      (node (ref "EPD_C10") (pin "2") (pinfunction "2_2") (pintype "passive"))
      (node (ref "J1") (pin "22") (pinfunction "22_22") (pintype "bidirectional"))
    )
    (net (code "29") (name "Net-(EPD_C12-Pad2)") (class "Default")
      (node (ref "EPD_C12") (pin "2") (pinfunction "2_2") (pintype "passive"))
      (node (ref "J1") (pin "24") (pinfunction "24_24") (pintype "bidirectional"))
    )
    (net (code "30") (name "Net-(IC1-TS{slash}MR)") (class "Default")
      (node (ref "IC1") (pin "D1") (pinfunction "TS/MR_D1") (pintype "bidirectional"))
      (node (ref "R9") (pin "2") (pinfunction "2_2") (pintype "bidirectional"))
    )
    (net (code "31") (name "Net-(IC2-REG)") (class "Default")
      (node (ref "C32") (pin "2") (pinfunction "2_2") (pintype "passive"))
      (node (ref "IC2") (pin "A2") (pinfunction "REG_A2") (pintype "bidirectional"))
    )
    (net (code "32") (name "Net-(IC3-SDO)") (class "Default")
      (node (ref "IC3") (pin "1") (pinfunction "SDO_1") (pintype "bidirectional"))
      (node (ref "R3") (pin "2") (pinfunction "2_2") (pintype "bidirectional"))
    )
    (net (code "33") (name "Net-(IC9-SCL)") (class "Default")
      (node (ref "IC9") (pin "D1") (pinfunction "SCL_D1") (pintype "bidirectional"))
      (node (ref "R4") (pin "2") (pinfunction "2_2") (pintype "bidirectional"))
    )
    (net (code "34") (name "Net-(IC9-SDA)") (class "Default")
      (node (ref "IC9") (pin "E1") (pinfunction "SDA_E1") (pintype "bidirectional"))
      (node (ref "R2") (pin "2") (pinfunction "2_2") (pintype "bidirectional"))
    )
    (net (code "35") (name "Net-(J4-CC1)") (class "Default")
      (node (ref "J4") (pin "A5") (pinfunction "CC1_A5") (pintype "bidirectional"))
      (node (ref "R1_USB") (pin "2") (pinfunction "2_2") (pintype "bidirectional"))
    )
    (net (code "36") (name "Net-(J4-CC2)") (class "Default")
      (node (ref "J4") (pin "B5") (pinfunction "CC2_B5") (pintype "bidirectional"))
      (node (ref "R2_USB") (pin "1") (pinfunction "1_1") (pintype "bidirectional"))
    )
    (net (code "37") (name "Net-(L2-Pad2)") (class "Default")
      (node (ref "L2") (pin "2") (pinfunction "2_2") (pintype "passive"))
      (node (ref "L3") (pin "1") (pinfunction "1_1") (pintype "passive"))
    )
    (net (code "38") (name "Net-(R1_EP_DR-Pad1)") (class "Default")
      (node (ref "R1_EP_DR") (pin "1") (pinfunction "1_1") (pintype "bidirectional"))
      (node (ref "R_TYPE_SEL") (pin "2") (pinfunction "2_2") (pintype "bidirectional"))
      (node (ref "SJ1") (pin "2") (pinfunction "2_2") (pintype "passive"))
    )
    (net (code "39") (name "Net-(U1-ANT)") (class "Default")
      (node (ref "C3") (pin "1") (pinfunction "1_1") (pintype "passive"))
      (node (ref "L1") (pin "1") (pinfunction "1_1") (pintype "passive"))
      (node (ref "U1") (pin "P$H23") (pinfunction "ANT_P$H23") (pintype "bidirectional"))
    )
    (net (code "40") (name "Net-(U1-DCC)") (class "Default")
      (node (ref "L2") (pin "1") (pinfunction "1_1") (pintype "passive"))
      (node (ref "U1") (pin "P$B3") (pinfunction "DCC_P$B3") (pintype "output"))
    )
    (net (code "41") (name "Net-(U1-DEC1)") (class "Default")
      (node (ref "C5") (pin "2") (pinfunction "2_2") (pintype "passive"))
      (node (ref "U1") (pin "P$C1") (pinfunction "DEC1_P$C1") (pintype "power_in"))
    )
    (net (code "42") (name "Net-(U1-DEC2)") (class "Default")
      (node (ref "C13") (pin "1") (pinfunction "1_1") (pintype "passive"))
      (node (ref "U1") (pin "P$A18") (pinfunction "DEC2_P$A18") (pintype "bidirectional"))
    )
    (net (code "43") (name "Net-(U1-DEC3)") (class "Default")
      (node (ref "C11") (pin "1") (pinfunction "1_1") (pintype "passive"))
      (node (ref "U1") (pin "P$D23") (pinfunction "DEC3_P$D23") (pintype "bidirectional"))
    )
    (net (code "44") (name "Net-(U1-DEC3V3)") (class "Default")
      (node (ref "C20") (pin "2") (pinfunction "2_2") (pintype "passive"))
      (node (ref "U1") (pin "P$AC5") (pinfunction "DEC3V3_P$AC5") (pintype "bidirectional"))
    )
    (net (code "45") (name "Net-(U1-DEC4)") (class "Default")
      (node (ref "C10") (pin "1") (pinfunction "1_1") (pintype "passive"))
      (node (ref "C15") (pin "1") (pinfunction "1_1") (pintype "passive"))
      (node (ref "C16") (pin "1") (pinfunction "1_1") (pintype "passive"))
      (node (ref "L3") (pin "2") (pinfunction "2_2") (pintype "passive"))
      (node (ref "U1") (pin "P$B5") (pinfunction "DEC4_P$B5") (pintype "power_in"))
      (node (ref "U1") (pin "P$E24") (pinfunction "DEC6_P$E24") (pintype "bidirectional"))
    )
    (net (code "46") (name "Net-(U1-DEC5)") (class "Default")
      (node (ref "C9") (pin "1") (pinfunction "1_1") (pintype "passive"))
      (node (ref "U1") (pin "P$N24") (pinfunction "DEC5_P$N24") (pintype "bidirectional"))
    )
    (net (code "47") (name "Net-(U1-P0.00{slash}XL1)") (class "Default")
      (node (ref "C17") (pin "2") (pinfunction "2_2") (pintype "passive"))
      (node (ref "U1") (pin "P$D2") (pinfunction "P0.00/XL1_P$D2") (pintype "bidirectional"))
      (node (ref "X2") (pin "1") (pinfunction "1_1") (pintype "passive"))
    )
    (net (code "48") (name "Net-(U1-P0.01{slash}XL2)") (class "Default")
      (node (ref "C18") (pin "2") (pinfunction "2_2") (pintype "passive"))
      (node (ref "U1") (pin "P$F2") (pinfunction "P0.01/XL2_P$F2") (pintype "bidirectional"))
      (node (ref "X2") (pin "2") (pinfunction "2_2") (pintype "passive"))
    )
    (net (code "49") (name "Net-(U1-XC1)") (class "Default")
      (node (ref "C1") (pin "1") (pinfunction "1_1") (pintype "passive"))
      (node (ref "U1") (pin "P$B24") (pinfunction "XC1_P$B24") (pintype "input"))
      (node (ref "X1") (pin "1") (pinfunction "1_1") (pintype "passive"))
    )
    (net (code "50") (name "Net-(U1-XC2)") (class "Default")
      (node (ref "C2") (pin "1") (pinfunction "1_1") (pintype "passive"))
      (node (ref "U1") (pin "P$A23") (pinfunction "XC2_P$A23") (pintype "output"))
      (node (ref "X1") (pin "3") (pinfunction "3_3") (pintype "passive"))
    )
    (net (code "51") (name "OUT+") (class "Default")
      (node (ref "IC2") (pin "A3") (pinfunction "OUT+_A3") (pintype "bidirectional"))
      (node (ref "TP_OP") (pin "TP") (pinfunction "TP_TP") (pintype "input"))
    )
    (net (code "52") (name "OUT-") (class "Default")
      (node (ref "IC2") (pin "C3") (pinfunction "OUT-_C3") (pintype "bidirectional"))
      (node (ref "TP_ON") (pin "TP") (pinfunction "TP_TP") (pintype "input"))
    )
    (net (code "53") (name "P0.04") (class "Default")
      (node (ref "U1") (pin "P$J1") (pinfunction "P0.04/AIN2_P$J1") (pintype "bidirectional"))
    )
    (net (code "54") (name "P0.09") (class "Default")
      (node (ref "U1") (pin "P$L24") (pinfunction "P0.09/NFC1_P$L24") (pintype "bidirectional"))
    )
    (net (code "55") (name "P0.13") (class "Default")
      (node (ref "C30") (pin "2") (pinfunction "2_2") (pintype "passive"))
      (node (ref "R1") (pin "1") (pinfunction "1_1") (pintype "bidirectional"))
      (node (ref "SW_UP") (pin "2") (pinfunction "2_2") (pintype "passive"))
      (node (ref "U1") (pin "P$AD8") (pinfunction "P0.13_P$AD8") (pintype "bidirectional"))
    )
    (net (code "56") (name "P0.14") (class "Default")
      (node (ref "C31") (pin "2") (pinfunction "2_2") (pintype "passive"))
      (node (ref "R8") (pin "1") (pinfunction "1_1") (pintype "bidirectional"))
      (node (ref "SW_ENT") (pin "2") (pinfunction "2_2") (pintype "passive"))
      (node (ref "U1") (pin "P$AC9") (pinfunction "P0.14_P$AC9") (pintype "bidirectional"))
    )
    (net (code "57") (name "P0.19") (class "Default")
      (node (ref "U1") (pin "P$AD16") (pinfunction "P0.20_P$AD16") (pintype "bidirectional"))
    )
    (net (code "58") (name "P0.20") (class "Default")
      (node (ref "U1") (pin "P$AC15") (pinfunction "P0.19_P$AC15") (pintype "bidirectional"))
    )
    (net (code "59") (name "P0.21") (class "Default")
      (node (ref "U1") (pin "P$AC17") (pinfunction "P0.21_P$AC17") (pintype "bidirectional"))
    )
    (net (code "60") (name "P0.22") (class "Default")
      (node (ref "U1") (pin "P$AD18") (pinfunction "P0.22_P$AD18") (pintype "bidirectional"))
    )
    (net (code "61") (name "P0.23") (class "Default")
      (node (ref "U1") (pin "P$AC19") (pinfunction "P0.23_P$AC19") (pintype "bidirectional"))
    )
    (net (code "62") (name "P0.24") (class "Default")
      (node (ref "U1") (pin "P$AD20") (pinfunction "P0.24_P$AD20") (pintype "bidirectional"))
    )
    (net (code "63") (name "P0.25") (class "Default")
      (node (ref "U1") (pin "P$AC21") (pinfunction "P0.25_P$AC21") (pintype "bidirectional"))
    )
    (net (code "64") (name "P0.26") (class "Default")
      (node (ref "U1") (pin "P$G1") (pinfunction "P0.26_P$G1") (pintype "bidirectional"))
    )
    (net (code "65") (name "P0.27") (class "Default")
      (node (ref "U1") (pin "P$H2") (pinfunction "P0.27_P$H2") (pintype "bidirectional"))
    )
    (net (code "66") (name "P0.28") (class "Default")
      (node (ref "U1") (pin "P$B11") (pinfunction "P0.28/AIN4_P$B11") (pintype "bidirectional"))
    )
    (net (code "67") (name "P0.29") (class "Default")
      (node (ref "U1") (pin "P$A10") (pinfunction "P0.29/AIN5_P$A10") (pintype "bidirectional"))
    )
    (net (code "68") (name "P0.30") (class "Default")
      (node (ref "U1") (pin "P$B9") (pinfunction "P0.30/AIN6_P$B9") (pintype "bidirectional"))
    )
    (net (code "69") (name "P0.31") (class "Default")
      (node (ref "U1") (pin "P$A8") (pinfunction "P0.31/AIN7_P$A8") (pintype "bidirectional"))
    )
    (net (code "70") (name "P1.01") (class "Default")
      (node (ref "Q1") (pin "1") (pinfunction "G_1") (pintype "bidirectional"))
      (node (ref "R_PWR_EPD") (pin "1") (pinfunction "1_1") (pintype "bidirectional"))
      (node (ref "U1") (pin "P$Y23") (pinfunction "P1.01_P$Y23") (pintype "bidirectional"))
    )
    (net (code "71") (name "P1.02") (class "Default")
      (node (ref "C29") (pin "2") (pinfunction "2_2") (pintype "passive"))
      (node (ref "R7") (pin "1") (pinfunction "1_1") (pintype "bidirectional"))
      (node (ref "SW_DN") (pin "2") (pinfunction "2_2") (pintype "passive"))
      (node (ref "U1") (pin "P$W24") (pinfunction "P1.02_P$W24") (pintype "bidirectional"))
    )
    (net (code "72") (name "P1.03") (class "Default")
      (node (ref "U1") (pin "P$V23") (pinfunction "P1.03_P$V23") (pintype "bidirectional"))
    )
    (net (code "73") (name "P1.04") (class "Default")
      (node (ref "U1") (pin "P$U24") (pinfunction "P1.04_P$U24") (pintype "bidirectional"))
    )
    (net (code "74") (name "P1.05") (class "Default")
      (node (ref "U1") (pin "P$T23") (pinfunction "P1.05_P$T23") (pintype "bidirectional"))
    )
    (net (code "75") (name "P1.06") (class "Default")
      (node (ref "U1") (pin "P$R24") (pinfunction "P1.06_P$R24") (pintype "bidirectional"))
    )
    (net (code "76") (name "P1.07") (class "Default")
      (node (ref "U1") (pin "P$P23") (pinfunction "P1.07_P$P23") (pintype "bidirectional"))
    )
    (net (code "77") (name "P1.09") (class "Default")
      (node (ref "U1") (pin "P$R1") (pinfunction "P1.09_P$R1") (pintype "bidirectional"))
    )
    (net (code "78") (name "P1.10") (class "Default")
      (node (ref "U1") (pin "P$A20") (pinfunction "P1.10_P$A20") (pintype "bidirectional"))
    )
    (net (code "79") (name "P1.11") (class "Default")
      (node (ref "U1") (pin "P$B19") (pinfunction "P1.11_P$B19") (pintype "bidirectional"))
    )
    (net (code "80") (name "P1.12") (class "Default")
      (node (ref "U1") (pin "P$B17") (pinfunction "P1.12_P$B17") (pintype "bidirectional"))
    )
    (net (code "81") (name "P1.13") (class "Default")
      (node (ref "U1") (pin "P$A16") (pinfunction "P1.13_P$A16") (pintype "bidirectional"))
    )
    (net (code "82") (name "P1.14") (class "Default")
      (node (ref "U1") (pin "P$B15") (pinfunction "P1.14_P$B15") (pintype "bidirectional"))
    )
    (net (code "83") (name "P1.15") (class "Default")
      (node (ref "U1") (pin "P$A14") (pinfunction "P1.15_P$A14") (pintype "bidirectional"))
    )
    (net (code "84") (name "PMIC_INT") (class "Default")
      (node (ref "IC1") (pin "A1") (pinfunction "~{INT}_A1") (pintype "bidirectional"))
      (node (ref "U1") (pin "P$T2") (pinfunction "P0.11_P$T2") (pintype "bidirectional"))
    )
    (net (code "85") (name "PREVGH") (class "Default")
      (node (ref "D5") (pin "1") (pinfunction "K_1") (pintype "bidirectional"))
      (node (ref "EPD_C9") (pin "2") (pinfunction "2_2") (pintype "passive"))
      (node (ref "J1") (pin "21") (pinfunction "21_21") (pintype "bidirectional"))
    )
    (net (code "86") (name "PREVGL") (class "Default")
      (node (ref "D2") (pin "2") (pinfunction "A_2") (pintype "bidirectional"))
      (node (ref "EPD_C11") (pin "2") (pinfunction "2_2") (pintype "passive"))
      (node (ref "J1") (pin "23") (pinfunction "23_23") (pintype "bidirectional"))
    )
    (net (code "87") (name "RESE") (class "Default")
      (node (ref "J1") (pin "3") (pinfunction "3_3") (pintype "bidirectional"))
      (node (ref "Q3") (pin "2") (pinfunction "S_2") (pintype "bidirectional"))
      (node (ref "R1_EP_DR") (pin "2") (pinfunction "2_2") (pintype "bidirectional"))
    )
    (net (code "88") (name "RESET") (class "Default")
      (node (ref "J2") (pin "6") (pinfunction "6_6") (pintype "bidirectional"))
      (node (ref "TP_RESET") (pin "TP") (pinfunction "TP_TP") (pintype "input"))
      (node (ref "U1") (pin "P$AC13") (pinfunction "P0.18/RESET_P$AC13") (pintype "bidirectional"))
    )
    (net (code "89") (name "SCK") (class "Default")
      (node (ref "J1") (pin "13") (pinfunction "13_13") (pintype "bidirectional"))
      (node (ref "U1") (pin "P$A12") (pinfunction "P0.02/AIN0_P$A12") (pintype "bidirectional"))
    )
    (net (code "90") (name "SCL") (class "Default")
      (node (ref "IC1") (pin "B1") (pinfunction "SCL_B1") (pintype "bidirectional"))
      (node (ref "IC2") (pin "C1") (pinfunction "SCL_C1") (pintype "bidirectional"))
      (node (ref "IC3") (pin "12") (pinfunction "SCX_12") (pintype "bidirectional"))
      (node (ref "R17") (pin "2") (pinfunction "2_2") (pintype "bidirectional"))
      (node (ref "R4") (pin "1") (pinfunction "1_1") (pintype "bidirectional"))
      (node (ref "TP_SCL") (pin "TP") (pinfunction "TP_TP") (pintype "input"))
      (node (ref "U1") (pin "P$M2") (pinfunction "P0.07_P$M2") (pintype "bidirectional"))
      (node (ref "U3") (pin "7") (pinfunction "SCL_7") (pintype "input"))
    )
    (net (code "91") (name "SDA") (class "Default")
      (node (ref "IC1") (pin "C1") (pinfunction "SDA_C1") (pintype "bidirectional"))
      (node (ref "IC2") (pin "B2") (pinfunction "SDA_B2") (pintype "bidirectional"))
      (node (ref "IC3") (pin "2") (pinfunction "SDX_2") (pintype "bidirectional"))
      (node (ref "R18") (pin "2") (pinfunction "2_2") (pintype "bidirectional"))
      (node (ref "R2") (pin "1") (pinfunction "1_1") (pintype "bidirectional"))
      (node (ref "TP_SDA") (pin "TP") (pinfunction "TP_TP") (pintype "input"))
      (node (ref "U1") (pin "P$L1") (pinfunction "P0.06_P$L1") (pintype "bidirectional"))
      (node (ref "U3") (pin "8") (pinfunction "SDA_8") (pintype "bidirectional"))
    )
    (net (code "92") (name "SWDCLK") (class "Default")
      (node (ref "J2") (pin "4") (pinfunction "4_4") (pintype "bidirectional"))
      (node (ref "TP_SWDCLK") (pin "TP") (pinfunction "TP_TP") (pintype "input"))
      (node (ref "U1") (pin "P$AA24") (pinfunction "SWDCLK_P$AA24") (pintype "input"))
    )
    (net (code "93") (name "SWDIO") (class "Default")
      (node (ref "J2") (pin "2") (pinfunction "2_2") (pintype "bidirectional"))
      (node (ref "TP_SWDIO") (pin "TP") (pinfunction "TP_TP") (pintype "input"))
      (node (ref "U1") (pin "P$AC24") (pinfunction "SWDIO_P$AC24") (pintype "bidirectional"))
    )
    (net (code "94") (name "SWO") (class "Default")
      (node (ref "TP_SWO") (pin "TP") (pinfunction "TP_TP") (pintype "input"))
      (node (ref "U1") (pin "P$AD22") (pinfunction "P1.00_P$AD22") (pintype "bidirectional"))
    )
    (net (code "95") (name "VBAT") (class "Default")
      (node (ref "C27") (pin "2") (pinfunction "2_2") (pintype "passive"))
      (node (ref "C37") (pin "2") (pinfunction "2_2") (pintype "passive"))
      (node (ref "IC1") (pin "C2") (pinfunction "BAT_C2") (pintype "bidirectional"))
      (node (ref "TP_VBAT") (pin "TP") (pinfunction "TP_TP") (pintype "input"))
      (node (ref "U3") (pin "2") (pinfunction "CELL_2") (pintype "power_in"))
      (node (ref "U3") (pin "3") (pinfunction "VDD_3") (pintype "power_in"))
    )
    (net (code "96") (name "VBUS") (class "Default")
      (node (ref "C21") (pin "1") (pinfunction "1_1") (pintype "passive"))
      (node (ref "C38") (pin "2") (pinfunction "2_2") (pintype "passive"))
      (node (ref "C42") (pin "1") (pinfunction "1_1") (pintype "passive"))
      (node (ref "C43") (pin "1") (pinfunction "1_1") (pintype "passive"))
      (node (ref "D3") (pin "5") (pinfunction "VBUS_5") (pintype "bidirectional"))
      (node (ref "IC1") (pin "A2") (pinfunction "IN_A2") (pintype "bidirectional"))
      (node (ref "J4") (pin "A4_B9") (pinfunction "VBUS_A4_B9") (pintype "power_in"))
      (node (ref "J4") (pin "A9_B4") (pinfunction "VBUS_A9_B4") (pintype "power_in"))
      (node (ref "U1") (pin "P$AD2") (pinfunction "VBUS_P$AD2") (pintype "power_in"))
    )
    (net (code "97") (name "VREG") (class "Default")
      (node (ref "C23") (pin "2") (pinfunction "2_2") (pintype "passive"))
      (node (ref "C24") (pin "2") (pinfunction "2_2") (pintype "passive"))
      (node (ref "C39") (pin "1") (pinfunction "1_1") (pintype "passive"))
      (node (ref "IC1") (pin "B2") (pinfunction "SYS_B2") (pintype "bidirectional"))
      (node (ref "IC9") (pin "A1") (pinfunction "EN_A1") (pintype "bidirectional"))
      (node (ref "IC9") (pin "A2") (pinfunction "VIN_1_A2") (pintype "bidirectional"))
      (node (ref "IC9") (pin "A3") (pinfunction "VIN_2_A3") (pintype "bidirectional"))
      (node (ref "TP_VREG") (pin "TP") (pinfunction "TP_TP") (pintype "input"))
    )
    (net (code "98") (name "unconnected-(ANT1-NC-Pad2)") (class "Default")
      (node (ref "ANT1") (pin "2") (pinfunction "NC_2") (pintype "no_connect"))
    )
    (net (code "99") (name "unconnected-(IC3-ASCL-Pad11)") (class "Default")
      (node (ref "IC3") (pin "11") (pinfunction "ASCL_11") (pintype "bidirectional"))
    )
    (net (code "100") (name "unconnected-(IC3-ASDA-Pad4)") (class "Default")
      (node (ref "IC3") (pin "4") (pinfunction "ASDA_4") (pintype "bidirectional"))
    )
    (net (code "101") (name "unconnected-(J1-Pad1)") (class "Default")
      (node (ref "J1") (pin "1") (pinfunction "1_1") (pintype "bidirectional"))
    )
    (net (code "102") (name "unconnected-(J1-Pad6)") (class "Default")
      (node (ref "J1") (pin "6") (pinfunction "6_6") (pintype "bidirectional"))
    )
    (net (code "103") (name "unconnected-(J1-Pad7)") (class "Default")
      (node (ref "J1") (pin "7") (pinfunction "7_7") (pintype "bidirectional"))
    )
    (net (code "104") (name "unconnected-(J4-SBU1-PadA8)") (class "Default")
      (node (ref "J4") (pin "A8") (pinfunction "SBU1_A8") (pintype "bidirectional"))
    )
    (net (code "105") (name "unconnected-(J4-SBU2-PadB8)") (class "Default")
      (node (ref "J4") (pin "B8") (pinfunction "SBU2_B8") (pintype "bidirectional"))
    )
    (net (code "106") (name "unconnected-(U1-DCCH-PadP$AB2)") (class "Default")
      (node (ref "U1") (pin "P$AB2") (pinfunction "DCCH_P$AB2") (pintype "bidirectional"))
    )
  )
)
